# ProgrammingInterface.net
KiCad netlist of a schematic drawn in Altium Designer
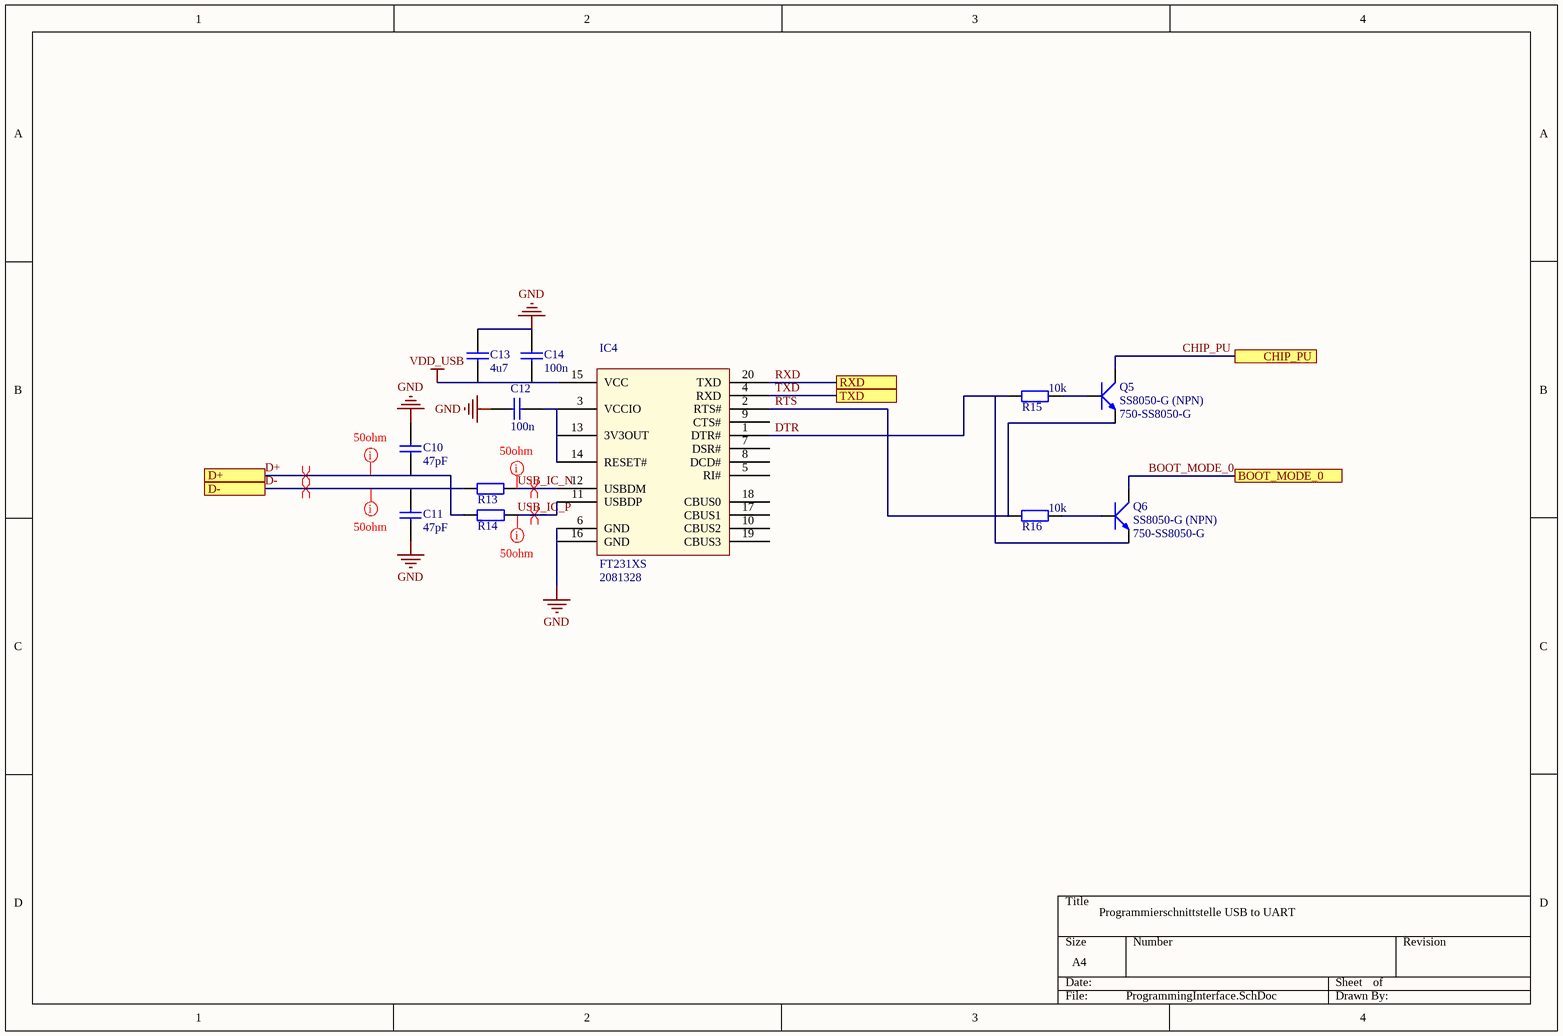
[diagram p0: ProgrammingInterface.SchDoc]

(export (version "E")
  (design (tool "Eeschema 10.0.6"))
  (components
    (comp (ref "C10")
      (value "47pF")
      (footprint "CAPC1005X55")
      (fields
        (field (name "MANUFACTURER") "Kemet")
        (field (name "VOLTAGE") "50V")
        (field (name "TOLERANCE") "±5%")
      )
      (libsource (lib "SCT_MySQL_5.1") (part "Capacitor"))
    )
    (comp (ref "C11")
      (value "47pF")
      (footprint "CAPC1005X55")
      (fields
        (field (name "MANUFACTURER") "Kemet")
        (field (name "VOLTAGE") "50V")
        (field (name "TOLERANCE") "±5%")
      )
      (libsource (lib "SCT_MySQL_5.1") (part "Capacitor"))
    )
    (comp (ref "C12")
      (value "100n")
      (footprint "CAPC1005X55")
      (fields
        (field (name "MANUFACTURER") "Kemet")
        (field (name "VOLTAGE") "16V")
        (field (name "TOLERANCE") "±15%")
      )
      (libsource (lib "SCT_MySQL_5.1") (part "Capacitor"))
    )
    (comp (ref "C13")
      (value "4u7")
      (footprint "CAPC1005X55")
      (description "Ceramic Chip Capacitor")
      (fields (field (name "MANUFACTURER") "Murata") (field (name "VOLTAGE") "6.3V"))
      (libsource (lib "SCT_MySQL_5.1") (part "Capacitor"))
    )
    (comp (ref "C14")
      (value "100n")
      (footprint "CAPC1005X55")
      (fields
        (field (name "MANUFACTURER") "Kemet")
        (field (name "VOLTAGE") "16V")
        (field (name "TOLERANCE") "±15%")
      )
      (libsource (lib "SCT_MySQL_5.1") (part "Capacitor"))
    )
    (comp (ref "IC4")
      (value "FT231XS")
      (footprint "SOP65P600X175-20")
      (description "USB to UART")
      (fields (field (name "MANUFACTURER") "FTDI") (field (name "SUPPLIER PART NUMBER 1") "2081328"))
      (libsource (lib "SCT_MySQL_5.1") (part "FT231XS"))
    )
    (comp (ref "Q5")
      (value "SS8050-G (NPN)")
      (footprint "SS8050-G (NPN)")
      (fields (field (name "SUPPLIER PART NUMBER 1") "750-SS8050-G"))
      (libsource (lib "Lib") (part "SS8050-G (NPN)"))
    )
    (comp (ref "Q6")
      (value "SS8050-G (NPN)")
      (footprint "SS8050-G (NPN)")
      (fields (field (name "SUPPLIER PART NUMBER 1") "750-SS8050-G"))
      (libsource (lib "Lib") (part "SS8050-G (NPN)"))
    )
    (comp (ref "R13")
      (value "~")
      (footprint "RESC1005X40")
      (description "Resistor")
      (fields (field (name "MANUFACTURER") "Multicomp") (field (name "TOLERANCE") "±1%"))
      (libsource (lib "SCT_MySQL_5.1") (part "Resistor"))
    )
    (comp (ref "R14")
      (value "~")
      (footprint "RESC1005X40")
      (description "Resistor")
      (fields (field (name "MANUFACTURER") "Multicomp") (field (name "TOLERANCE") "±1%"))
      (libsource (lib "SCT_MySQL_5.1") (part "Resistor"))
    )
    (comp (ref "R15")
      (value "10k")
      (footprint "RESC1005X40")
      (description "Resistor")
      (fields (field (name "MANUFACTURER") "Multicomp") (field (name "TOLERANCE") "±1%"))
      (libsource (lib "SCT_MySQL_5.1") (part "Resistor"))
    )
    (comp (ref "R16")
      (value "10k")
      (footprint "RESC1005X40")
      (description "Resistor")
      (fields (field (name "MANUFACTURER") "Multicomp") (field (name "TOLERANCE") "±1%"))
      (libsource (lib "SCT_MySQL_5.1") (part "Resistor"))
    )
  )
  (nets
    (net (code "1") (name "/BOOT_MODE_0") (class "Default")
      (node (ref "Q6") (pin "3") (pinfunction "Collector_3") (pintype "passive"))
    )
    (net (code "2") (name "/CHIP_PU") (class "Default")
      (node (ref "Q5") (pin "3") (pinfunction "Collector_3") (pintype "passive"))
    )
    (net (code "3") (name "/D+") (class "Default")
      (node (ref "C10") (pin "1") (pinfunction "1_1") (pintype "passive"))
      (node (ref "R14") (pin "1") (pinfunction "1_1") (pintype "passive"))
    )
    (net (code "4") (name "/D-") (class "Default")
      (node (ref "C11") (pin "2") (pinfunction "2_2") (pintype "passive"))
      (node (ref "R13") (pin "1") (pinfunction "1_1") (pintype "passive"))
    )
    (net (code "5") (name "/DTR") (class "Default")
      (node (ref "IC4") (pin "1") (pinfunction "DTR#_1") (pintype "passive"))
      (node (ref "Q6") (pin "2") (pinfunction "Emitter_2") (pintype "passive"))
      (node (ref "R15") (pin "1") (pinfunction "1_1") (pintype "passive"))
    )
    (net (code "6") (name "/RTS") (class "Default")
      (node (ref "IC4") (pin "2") (pinfunction "RTS#_2") (pintype "passive"))
      (node (ref "Q5") (pin "2") (pinfunction "Emitter_2") (pintype "passive"))
      (node (ref "R16") (pin "1") (pinfunction "1_1") (pintype "passive"))
    )
    (net (code "7") (name "/RXD") (class "Default")
      (node (ref "IC4") (pin "20") (pinfunction "TXD_20") (pintype "passive"))
    )
    (net (code "8") (name "/TXD") (class "Default")
      (node (ref "IC4") (pin "4") (pinfunction "RXD_4") (pintype "passive"))
    )
    (net (code "9") (name "/USB_IC_N") (class "Default")
      (node (ref "IC4") (pin "12") (pinfunction "USBDM_12") (pintype "passive"))
      (node (ref "R13") (pin "2") (pinfunction "2_2") (pintype "passive"))
    )
    (net (code "10") (name "/USB_IC_P") (class "Default")
      (node (ref "IC4") (pin "11") (pinfunction "USBDP_11") (pintype "passive"))
      (node (ref "R14") (pin "2") (pinfunction "2_2") (pintype "passive"))
    )
    (net (code "11") (name "GND") (class "Default")
      (node (ref "C10") (pin "2") (pinfunction "2_2") (pintype "passive"))
      (node (ref "C11") (pin "1") (pinfunction "1_1") (pintype "passive"))
      (node (ref "C12") (pin "1") (pinfunction "1_1") (pintype "passive"))
      (node (ref "C13") (pin "2") (pinfunction "2_2") (pintype "passive"))
      (node (ref "C14") (pin "2") (pinfunction "2_2") (pintype "passive"))
      (node (ref "IC4") (pin "16") (pinfunction "GND_16") (pintype "passive"))
      (node (ref "IC4") (pin "6") (pinfunction "GND_6") (pintype "passive"))
    )
    (net (code "12") (name "Net-(IC4-3V3OUT)") (class "Default")
      (node (ref "C12") (pin "2") (pinfunction "2_2") (pintype "passive"))
      (node (ref "IC4") (pin "13") (pinfunction "3V3OUT_13") (pintype "passive"))
      (node (ref "IC4") (pin "14") (pinfunction "RESET#_14") (pintype "passive"))
      (node (ref "IC4") (pin "3") (pinfunction "VCCIO_3") (pintype "passive"))
    )
    (net (code "13") (name "Net-(Q5-Base)") (class "Default")
      (node (ref "Q5") (pin "1") (pinfunction "Base_1") (pintype "passive"))
      (node (ref "R15") (pin "2") (pinfunction "2_2") (pintype "passive"))
    )
    (net (code "14") (name "Net-(Q6-Base)") (class "Default")
      (node (ref "Q6") (pin "1") (pinfunction "Base_1") (pintype "passive"))
      (node (ref "R16") (pin "2") (pinfunction "2_2") (pintype "passive"))
    )
    (net (code "15") (name "VDD_USB") (class "Default")
      (node (ref "C13") (pin "1") (pinfunction "1_1") (pintype "passive"))
      (node (ref "C14") (pin "1") (pinfunction "1_1") (pintype "passive"))
      (node (ref "IC4") (pin "15") (pinfunction "VCC_15") (pintype "passive"))
    )
    (net (code "16") (name "unconnected-(IC4-CBUS0-Pad18)") (class "Default")
      (node (ref "IC4") (pin "18") (pinfunction "CBUS0_18") (pintype "passive"))
    )
    (net (code "17") (name "unconnected-(IC4-CBUS1-Pad17)") (class "Default")
      (node (ref "IC4") (pin "17") (pinfunction "CBUS1_17") (pintype "passive"))
    )
    (net (code "18") (name "unconnected-(IC4-CBUS2-Pad10)") (class "Default")
      (node (ref "IC4") (pin "10") (pinfunction "CBUS2_10") (pintype "passive"))
    )
    (net (code "19") (name "unconnected-(IC4-CBUS3-Pad19)") (class "Default")
      (node (ref "IC4") (pin "19") (pinfunction "CBUS3_19") (pintype "passive"))
    )
    (net (code "20") (name "unconnected-(IC4-CTS#-Pad9)") (class "Default")
      (node (ref "IC4") (pin "9") (pinfunction "CTS#_9") (pintype "passive"))
    )
    (net (code "21") (name "unconnected-(IC4-DCD#-Pad8)") (class "Default")
      (node (ref "IC4") (pin "8") (pinfunction "DCD#_8") (pintype "passive"))
    )
    (net (code "22") (name "unconnected-(IC4-DSR#-Pad7)") (class "Default")
      (node (ref "IC4") (pin "7") (pinfunction "DSR#_7") (pintype "passive"))
    )
    (net (code "23") (name "unconnected-(IC4-RI#-Pad5)") (class "Default")
      (node (ref "IC4") (pin "5") (pinfunction "RI#_5") (pintype "passive"))
    )
  )
)
